# untitled.net
KiCad netlist of a schematic drawn in EAGLE
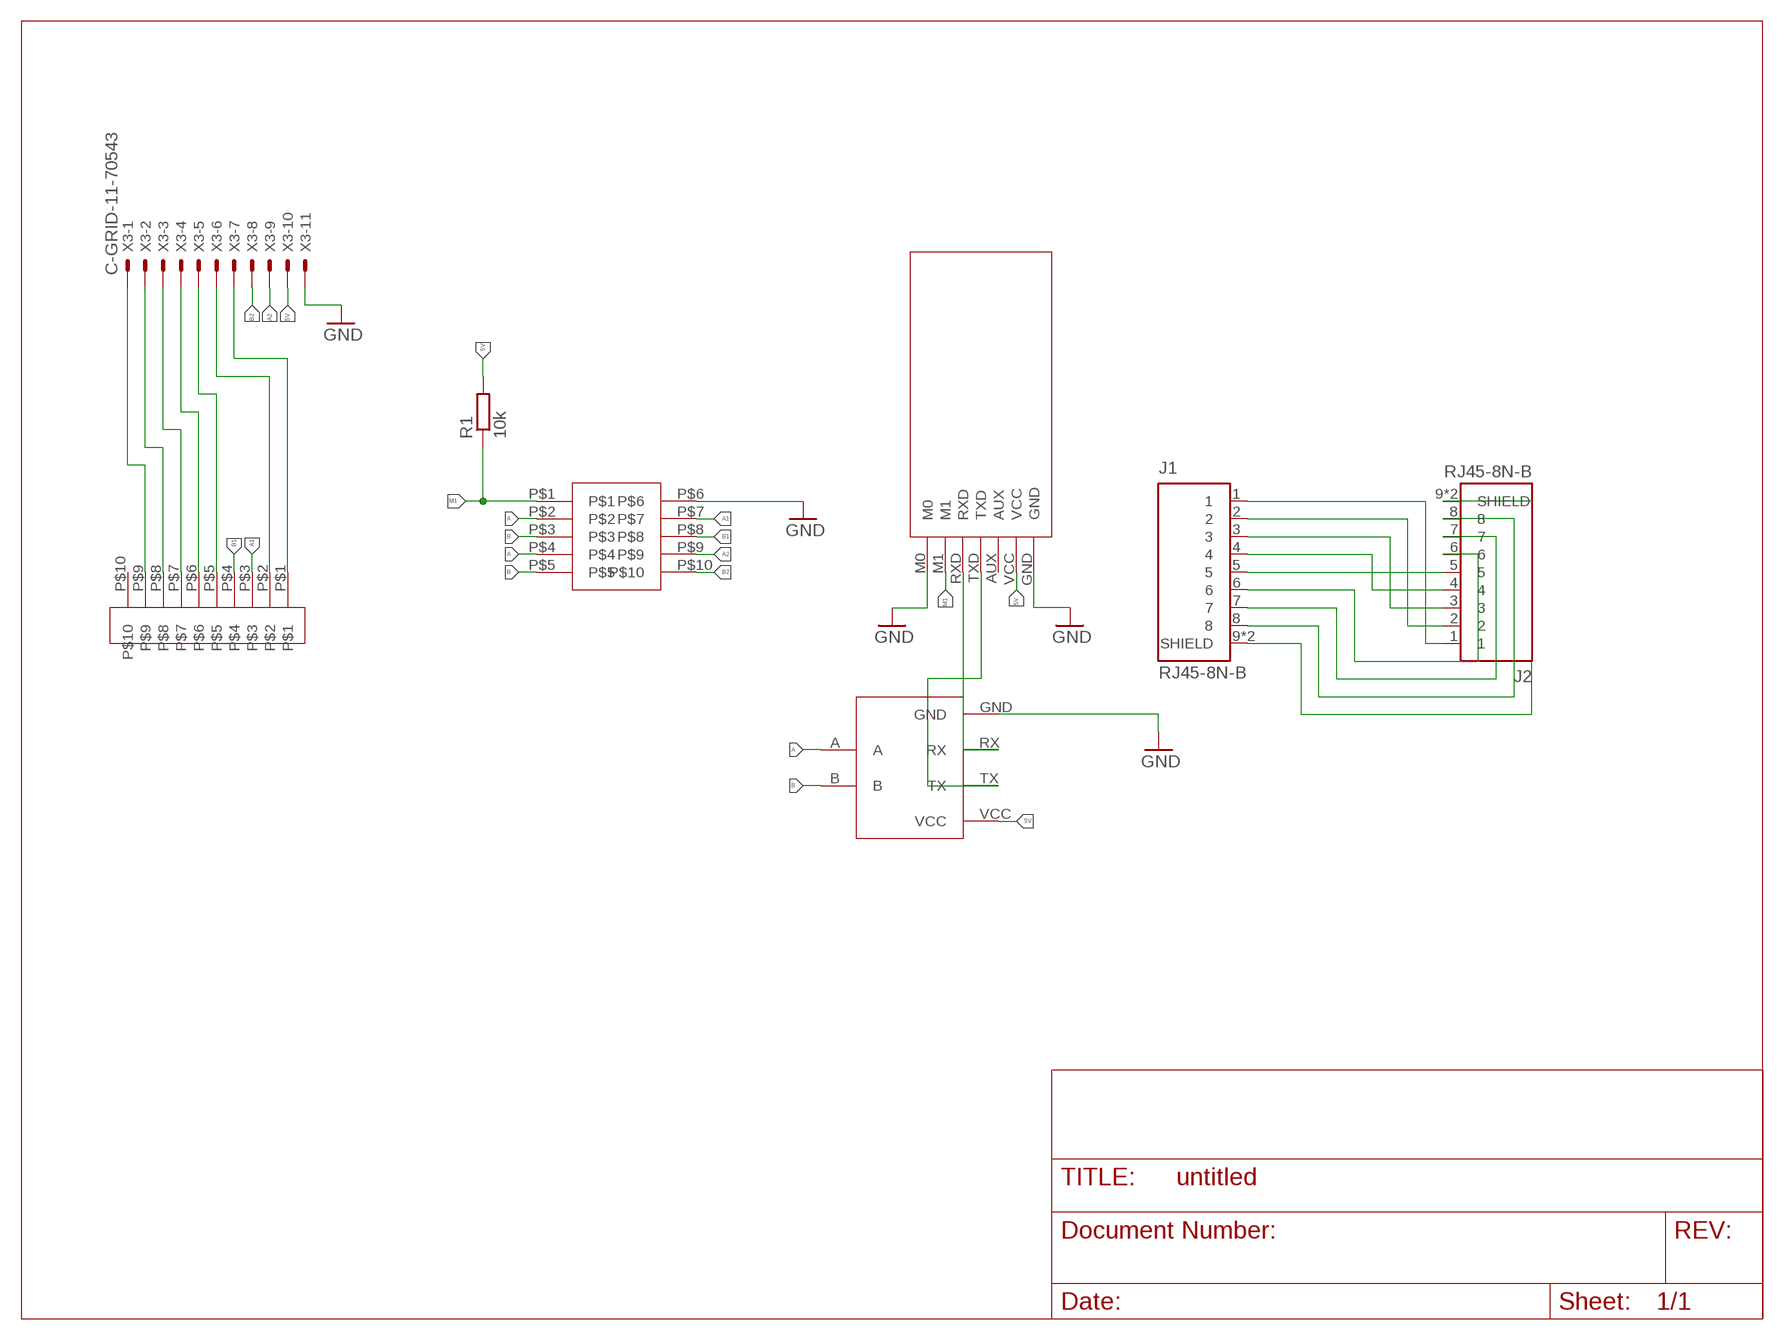
[diagram p0: schematic, sheet 1]

(export (version "E")
  (design (tool "Eeschema 10.0.6"))
  (components
    (comp (ref "DP-05RP1")
      (value "DP-05RP")
      (footprint "eagle-import:DP-05RP")
      (libsource (lib "eagle-import") (part "DP-05RP"))
    )
    (comp (ref "EBYTEE220-900T22D1")
      (value "EBYTEE220-900T22D")
      (footprint "eagle-import:EBYTEE220-900T22D")
      (libsource (lib "eagle-import") (part "EBYTEE220-900T22D"))
    )
    (comp (ref "J1")
      (value "RJ45-8N-B")
      (footprint "eagle-import:TE_RJ45-8N-B")
      (fields (field (name "MF") "TE Connectivity"))
      (libsource (lib "eagle-import") (part "RJ45-8N-B"))
    )
    (comp (ref "J2")
      (value "RJ45-8N-B")
      (footprint "eagle-import:TE_RJ45-8N-B")
      (fields (field (name "MF") "TE Connectivity"))
      (libsource (lib "eagle-import") (part "RJ45-8N-B"))
    )
    (comp (ref "KONEKTOR-3.81-13P1")
      (value "KONEKTOR-3.81-13P")
      (footprint "eagle-import:KONEKTOR-3.81-13P")
      (libsource (lib "eagle-import") (part "KONEKTOR-3.81-13P"))
    )
    (comp (ref "R1")
      (value "10k")
      (footprint "eagle-import:R0805")
      (libsource (lib "eagle-import") (part "R-EU_R0805"))
    )
    (comp (ref "TTL-RS1")
      (value "TTL-RS485")
      (footprint "eagle-import:TTL-RS485")
      (libsource (lib "eagle-import") (part "TTL-RS485"))
    )
    (comp (ref "X3")
      (value "C-GRID-11-70543")
      (footprint "eagle-import:70543-11")
      (fields (field (name "MF") "MOLEX"))
      (libsource (lib "eagle-import") (part "C-GRID-11-70543"))
    )
  )
  (nets
    (net (code "1") (name "5V") (class "Default")
      (node (ref "EBYTEE220-900T22D1") (pin "VCC") (pinfunction "VCC_VCC") (pintype "bidirectional"))
      (node (ref "R1") (pin "2") (pinfunction "2_2") (pintype "passive"))
      (node (ref "TTL-RS1") (pin "VCC") (pinfunction "VCC_VCC") (pintype "bidirectional"))
      (node (ref "X3") (pin "10") (pinfunction "S_10") (pintype "passive"))
    )
    (net (code "2") (name "A") (class "Default")
      (node (ref "DP-05RP1") (pin "P$2") (pinfunction "P$2_P$2") (pintype "bidirectional"))
      (node (ref "DP-05RP1") (pin "P$4") (pinfunction "P$4_P$4") (pintype "bidirectional"))
      (node (ref "TTL-RS1") (pin "A") (pinfunction "A_A") (pintype "bidirectional"))
    )
    (net (code "3") (name "A1") (class "Default")
      (node (ref "DP-05RP1") (pin "P$7") (pinfunction "P$7_P$7") (pintype "bidirectional"))
      (node (ref "KONEKTOR-3.81-13P1") (pin "P$3") (pinfunction "P$3_P$3") (pintype "bidirectional"))
    )
    (net (code "4") (name "A2") (class "Default")
      (node (ref "DP-05RP1") (pin "P$9") (pinfunction "P$9_P$9") (pintype "bidirectional"))
      (node (ref "X3") (pin "9") (pinfunction "S_9") (pintype "passive"))
    )
    (net (code "5") (name "B") (class "Default")
      (node (ref "DP-05RP1") (pin "P$3") (pinfunction "P$3_P$3") (pintype "bidirectional"))
      (node (ref "DP-05RP1") (pin "P$5") (pinfunction "P$5_P$5") (pintype "bidirectional"))
      (node (ref "TTL-RS1") (pin "B") (pinfunction "B_B") (pintype "bidirectional"))
    )
    (net (code "6") (name "B1") (class "Default")
      (node (ref "DP-05RP1") (pin "P$8") (pinfunction "P$8_P$8") (pintype "bidirectional"))
      (node (ref "KONEKTOR-3.81-13P1") (pin "P$4") (pinfunction "P$4_P$4") (pintype "bidirectional"))
    )
    (net (code "7") (name "B2") (class "Default")
      (node (ref "DP-05RP1") (pin "P$10") (pinfunction "P$10_P$10") (pintype "bidirectional"))
      (node (ref "X3") (pin "8") (pinfunction "S_8") (pintype "passive"))
    )
    (net (code "8") (name "GND") (class "Default")
      (node (ref "DP-05RP1") (pin "P$6") (pinfunction "P$6_P$6") (pintype "bidirectional"))
      (node (ref "EBYTEE220-900T22D1") (pin "GND") (pinfunction "GND_GND") (pintype "bidirectional"))
      (node (ref "EBYTEE220-900T22D1") (pin "M0") (pinfunction "M0_M0") (pintype "bidirectional"))
      (node (ref "TTL-RS1") (pin "GND") (pinfunction "GND_GND") (pintype "bidirectional"))
      (node (ref "X3") (pin "11") (pinfunction "S_11") (pintype "passive"))
    )
    (net (code "9") (name "M1") (class "Default")
      (node (ref "DP-05RP1") (pin "P$1") (pinfunction "P$1_P$1") (pintype "bidirectional"))
      (node (ref "EBYTEE220-900T22D1") (pin "M1") (pinfunction "M1_M1") (pintype "bidirectional"))
      (node (ref "R1") (pin "1") (pinfunction "1_1") (pintype "passive"))
    )
    (net (code "10") (name "Net-(EBYTEE220-900T22D1-PadRXD)") (class "Default")
      (node (ref "EBYTEE220-900T22D1") (pin "RXD") (pinfunction "RXD_RXD") (pintype "bidirectional"))
      (node (ref "TTL-RS1") (pin "RX") (pinfunction "RX_RX") (pintype "bidirectional"))
    )
    (net (code "11") (name "Net-(EBYTEE220-900T22D1-PadTXD)") (class "Default")
      (node (ref "EBYTEE220-900T22D1") (pin "TXD") (pinfunction "TXD_TXD") (pintype "bidirectional"))
      (node (ref "TTL-RS1") (pin "TX") (pinfunction "TX_TX") (pintype "bidirectional"))
    )
    (net (code "12") (name "Net-(J1-Pad1)") (class "Default")
      (node (ref "J1") (pin "1") (pinfunction "1_1") (pintype "passive"))
      (node (ref "J2") (pin "1") (pinfunction "1_1") (pintype "passive"))
    )
    (net (code "13") (name "Net-(J1-Pad2)") (class "Default")
      (node (ref "J1") (pin "2") (pinfunction "2_2") (pintype "passive"))
      (node (ref "J2") (pin "2") (pinfunction "2_2") (pintype "passive"))
    )
    (net (code "14") (name "Net-(J1-Pad3)") (class "Default")
      (node (ref "J1") (pin "3") (pinfunction "3_3") (pintype "passive"))
      (node (ref "J2") (pin "3") (pinfunction "3_3") (pintype "passive"))
    )
    (net (code "15") (name "Net-(J1-Pad4)") (class "Default")
      (node (ref "J1") (pin "4") (pinfunction "4_4") (pintype "passive"))
      (node (ref "J2") (pin "4") (pinfunction "4_4") (pintype "passive"))
    )
    (net (code "16") (name "Net-(J1-Pad5)") (class "Default")
      (node (ref "J1") (pin "5") (pinfunction "5_5") (pintype "passive"))
      (node (ref "J2") (pin "5") (pinfunction "5_5") (pintype "passive"))
    )
    (net (code "17") (name "Net-(J1-Pad6)") (class "Default")
      (node (ref "J1") (pin "6") (pinfunction "6_6") (pintype "passive"))
      (node (ref "J2") (pin "6") (pinfunction "6_6") (pintype "passive"))
    )
    (net (code "18") (name "Net-(J1-Pad7)") (class "Default")
      (node (ref "J1") (pin "7") (pinfunction "7_7") (pintype "passive"))
      (node (ref "J2") (pin "7") (pinfunction "7_7") (pintype "passive"))
    )
    (net (code "19") (name "Net-(J1-Pad8)") (class "Default")
      (node (ref "J1") (pin "8") (pinfunction "8_8") (pintype "passive"))
      (node (ref "J2") (pin "8") (pinfunction "8_8") (pintype "passive"))
    )
    (net (code "20") (name "Net-(J1-SHIELD-Pad10)") (class "Default")
      (node (ref "J1") (pin "10") (pinfunction "SHIELD_10") (pintype "passive"))
      (node (ref "J1") (pin "9") (pinfunction "SHIELD_9") (pintype "passive"))
      (node (ref "J2") (pin "10") (pinfunction "SHIELD_10") (pintype "passive"))
      (node (ref "J2") (pin "9") (pinfunction "SHIELD_9") (pintype "passive"))
    )
    (net (code "21") (name "Net-(X3A-S)") (class "Default")
      (node (ref "KONEKTOR-3.81-13P1") (pin "P$9") (pinfunction "P$9_P$9") (pintype "bidirectional"))
      (node (ref "X3") (pin "1") (pinfunction "S_1") (pintype "passive"))
    )
    (net (code "22") (name "Net-(X3D-S)") (class "Default")
      (node (ref "KONEKTOR-3.81-13P1") (pin "P$8") (pinfunction "P$8_P$8") (pintype "bidirectional"))
      (node (ref "X3") (pin "2") (pinfunction "S_2") (pintype "passive"))
    )
    (net (code "23") (name "Net-(X3E-S)") (class "Default")
      (node (ref "KONEKTOR-3.81-13P1") (pin "P$7") (pinfunction "P$7_P$7") (pintype "bidirectional"))
      (node (ref "X3") (pin "3") (pinfunction "S_3") (pintype "passive"))
    )
    (net (code "24") (name "Net-(X3F-S)") (class "Default")
      (node (ref "KONEKTOR-3.81-13P1") (pin "P$6") (pinfunction "P$6_P$6") (pintype "bidirectional"))
      (node (ref "X3") (pin "4") (pinfunction "S_4") (pintype "passive"))
    )
    (net (code "25") (name "Net-(X3G-S)") (class "Default")
      (node (ref "KONEKTOR-3.81-13P1") (pin "P$5") (pinfunction "P$5_P$5") (pintype "bidirectional"))
      (node (ref "X3") (pin "5") (pinfunction "S_5") (pintype "passive"))
    )
    (net (code "26") (name "Net-(X3H-S)") (class "Default")
      (node (ref "KONEKTOR-3.81-13P1") (pin "P$2") (pinfunction "P$2_P$2") (pintype "bidirectional"))
      (node (ref "X3") (pin "6") (pinfunction "S_6") (pintype "passive"))
    )
    (net (code "27") (name "Net-(X3I-S)") (class "Default")
      (node (ref "KONEKTOR-3.81-13P1") (pin "P$1") (pinfunction "P$1_P$1") (pintype "bidirectional"))
      (node (ref "X3") (pin "7") (pinfunction "S_7") (pintype "passive"))
    )
    (net (code "28") (name "unconnected-(EBYTEE220-900T22D1-PadAUX)") (class "Default")
      (node (ref "EBYTEE220-900T22D1") (pin "AUX") (pinfunction "AUX_AUX") (pintype "bidirectional"))
    )
    (net (code "29") (name "unconnected-(KONEKTOR-3.81-13P1-PadP$10)") (class "Default")
      (node (ref "KONEKTOR-3.81-13P1") (pin "P$10") (pinfunction "P$10_P$10") (pintype "bidirectional"))
    )
  )
)
